# GD_Tcontroller_PWM.net
KiCad netlist of a schematic drawn in Altium Designer
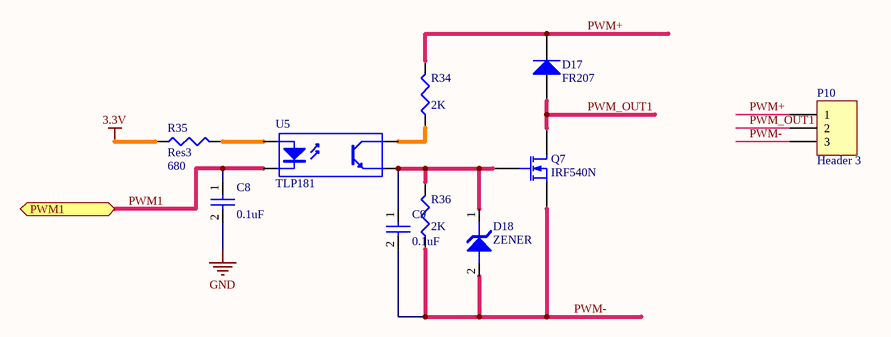
[diagram p0: GD_Tcontroller_PWM.SchDoc]

(export (version "E")
  (design (tool "Eeschema 10.0.6"))
  (components
    (comp (ref "C8")
      (value "0.1uF")
      (footprint "C0805")
      (description "CAP SMD CR X7R 50V 10% 0.1uF 0805 ROHS")
      (fields (field (name "MANUFACTURER") "YAGEO") (field (name "Comment") "CAP"))
      (libsource (lib "enlogic") (part "CAP"))
    )
    (comp (ref "C9")
      (value "0.1uF")
      (footprint "C0805")
      (description "CAP SMD CR X7R 50V 10% 0.1uF 0805 ROHS")
      (fields (field (name "MANUFACTURER") "YAGEO") (field (name "Comment") "CAP"))
      (libsource (lib "enlogic") (part "CAP"))
    )
    (comp (ref "D17")
      (value "FR207")
      (footprint "ONSC-AXIAL_LEAD-2-59AA-01_P")
      (description "Default Diode")
      (fields (field (name "PUBLISHER") "Altium Limited"))
      (libsource (lib "Miscellaneous Devices") (part "Diode"))
    )
    (comp (ref "D18")
      (value "ZENER")
      (footprint "SMB")
      (fields (field (name "MANUFACTURER") "Bourns"))
      (libsource (lib "Enlogic") (part "ZENER"))
    )
    (comp (ref "P10")
      (value "Header 3")
      (footprint "HT5.08-3P-H")
      (description "Header, 3-Pin")
      (fields (field (name "PUBLISHER") "Altium Limited"))
      (libsource (lib "Miscellaneous Connectors") (part "Header 3"))
    )
    (comp (ref "Q7")
      (value "IRF540N")
      (footprint "ONSC-TO-220-3-221A-09_AF")
      (description "N-Channel MOSFET")
      (fields (field (name "PUBLISHER") "Altium Limited"))
      (libsource (lib "Miscellaneous Devices") (part "MOSFET-N"))
    )
    (comp (ref "R34")
      (value "2K")
      (footprint "R1206")
      (description "Resistor")
      (fields (field (name "Comment") "Res3") (field (name "PUBLISHER") "Altium Limited"))
      (libsource (lib "Miscellaneous Devices") (part "Res3"))
    )
    (comp (ref "R35")
      (value "Res3")
      (footprint "R1206")
      (description "Resistor")
      (fields (field (name "ALTIUM_VALUE") "680") (field (name "PUBLISHER") "Altium Limited"))
      (libsource (lib "Miscellaneous Devices") (part "Res3"))
    )
    (comp (ref "R36")
      (value "2K")
      (footprint "R1206")
      (description "Resistor")
      (fields (field (name "Comment") "Res3") (field (name "PUBLISHER") "Altium Limited"))
      (libsource (lib "Miscellaneous Devices") (part "Res3"))
    )
    (comp (ref "U5")
      (value "TLP181")
      (footprint "TLP181")
      (description "4-Pin Phototransistor Optocoupler")
      (fields (field (name "PUBLISHER") "Altium Limited"))
      (libsource (lib "Miscellaneous Devices") (part "Optoisolator1"))
    )
  )
  (nets
    (net (code "1") (name "/PWM+") (class "Default")
      (node (ref "D17") (pin "2") (pinfunction "K_2") (pintype "passive"))
      (node (ref "P10") (pin "1") (pinfunction "1_1") (pintype "passive"))
      (node (ref "R34") (pin "2") (pinfunction "2_2") (pintype "passive"))
    )
    (net (code "2") (name "/PWM-") (class "Default")
      (node (ref "C9") (pin "2") (pinfunction "2_2") (pintype "passive"))
      (node (ref "D18") (pin "2") (pintype "passive"))
      (node (ref "P10") (pin "3") (pinfunction "3_3") (pintype "passive"))
      (node (ref "Q7") (pin "3") (pinfunction "S_3") (pintype "passive"))
      (node (ref "R36") (pin "1") (pinfunction "1_1") (pintype "passive"))
    )
    (net (code "3") (name "/PWM1") (class "Default")
      (node (ref "C8") (pin "1") (pinfunction "1_1") (pintype "passive"))
      (node (ref "U5") (pin "2") (pinfunction "K_2") (pintype "passive"))
    )
    (net (code "4") (name "/PWM_OUT1") (class "Default")
      (node (ref "D17") (pin "1") (pinfunction "A_1") (pintype "passive"))
      (node (ref "P10") (pin "2") (pinfunction "2_2") (pintype "passive"))
      (node (ref "Q7") (pin "1") (pinfunction "D_1") (pintype "passive"))
    )
    (net (code "5") (name "3.3V") (class "Default")
      (node (ref "R35") (pin "1") (pinfunction "1_1") (pintype "passive"))
    )
    (net (code "6") (name "GND") (class "Default")
      (node (ref "C8") (pin "2") (pinfunction "2_2") (pintype "passive"))
    )
    (net (code "7") (name "Net-(Q7-G)") (class "Default")
      (node (ref "C9") (pin "1") (pinfunction "1_1") (pintype "passive"))
      (node (ref "D18") (pin "1") (pintype "passive"))
      (node (ref "Q7") (pin "2") (pinfunction "G_2") (pintype "passive"))
      (node (ref "R36") (pin "2") (pinfunction "2_2") (pintype "passive"))
      (node (ref "U5") (pin "3") (pinfunction "E_3") (pintype "passive"))
    )
    (net (code "8") (name "Net-(U5-A)") (class "Default")
      (node (ref "R35") (pin "2") (pinfunction "2_2") (pintype "passive"))
      (node (ref "U5") (pin "1") (pinfunction "A_1") (pintype "passive"))
    )
    (net (code "9") (name "Net-(U5-C)") (class "Default")
      (node (ref "R34") (pin "1") (pinfunction "1_1") (pintype "passive"))
      (node (ref "U5") (pin "4") (pinfunction "C_4") (pintype "passive"))
    )
  )
)
